# tiny45-button-2-leds.net
KiCad netlist of a schematic drawn in EAGLE
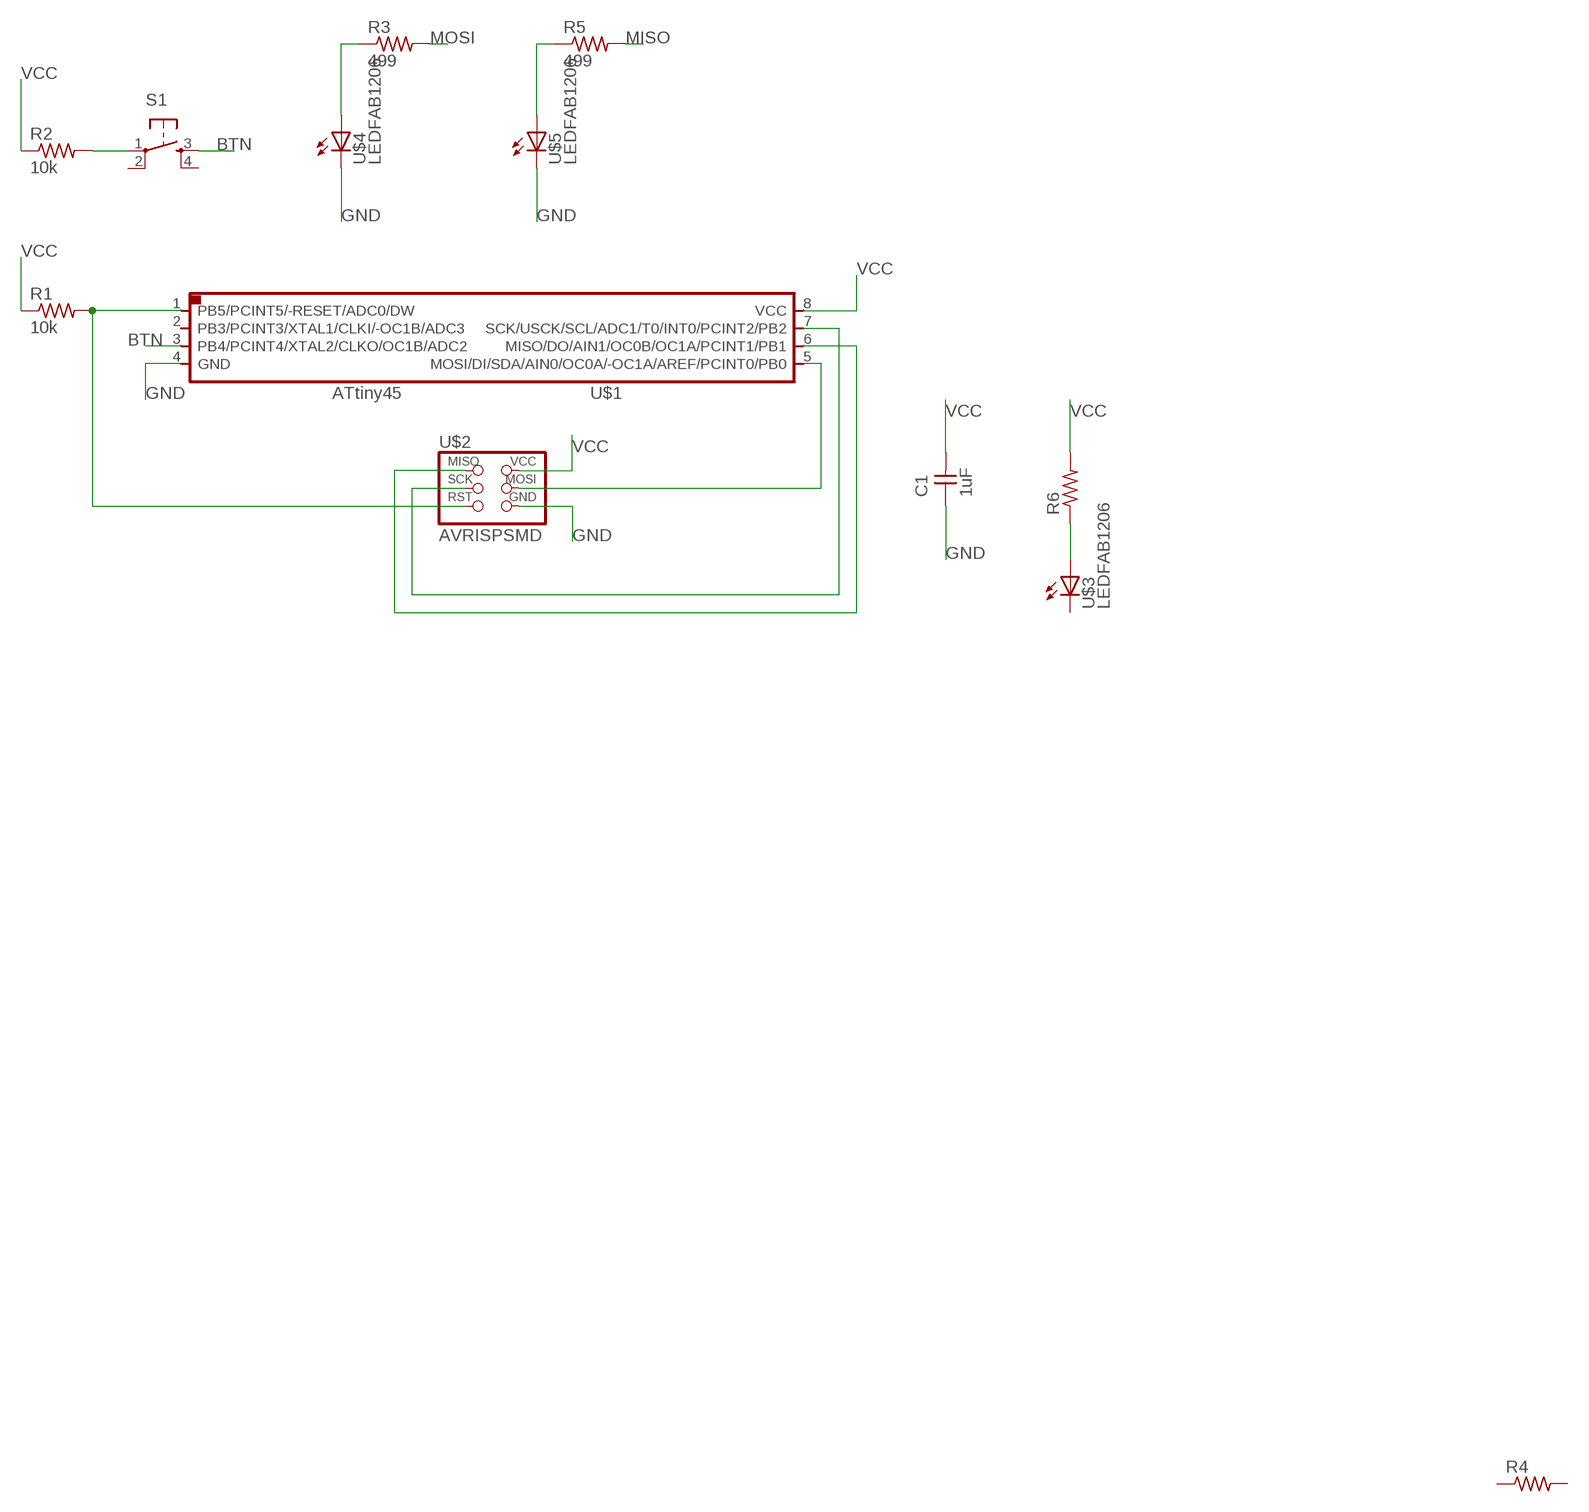
[diagram p0: schematic, sheet 1]

(export (version "E")
  (design (tool "Eeschema 10.0.6"))
  (components
    (comp (ref "C1")
      (value "1uF")
      (footprint "eagle-import:C1206FAB")
      (libsource (lib "eagle-import") (part "CAP-UNPOLARIZEDFAB"))
    )
    (comp (ref "R1")
      (value "10k")
      (footprint "eagle-import:R1206FAB")
      (libsource (lib "eagle-import") (part "RES-US1206FAB"))
    )
    (comp (ref "R2")
      (value "10k")
      (footprint "eagle-import:R1206FAB")
      (libsource (lib "eagle-import") (part "RES-US1206FAB"))
    )
    (comp (ref "R3")
      (value "499")
      (footprint "eagle-import:R1206FAB")
      (libsource (lib "eagle-import") (part "RES-US1206FAB"))
    )
    (comp (ref "R4")
      (value "RES-US1206FAB")
      (footprint "eagle-import:R1206FAB")
      (libsource (lib "eagle-import") (part "RES-US1206FAB"))
    )
    (comp (ref "R5")
      (value "499")
      (footprint "eagle-import:R1206FAB")
      (libsource (lib "eagle-import") (part "RES-US1206FAB"))
    )
    (comp (ref "R6")
      (value "RES-US1206FAB")
      (footprint "eagle-import:R1206FAB")
      (libsource (lib "eagle-import") (part "RES-US1206FAB"))
    )
    (comp (ref "S1")
      (value "6MM_SWITCH6MM_SWITCH")
      (footprint "eagle-import:6MM_SWITCH")
      (libsource (lib "eagle-import") (part "6MM_SWITCH6MM_SWITCH"))
    )
    (comp (ref "U$1")
      (value "ATTINY45SI")
      (footprint "eagle-import:SOIC8")
      (libsource (lib "eagle-import") (part "ATTINY45SI"))
    )
    (comp (ref "U$2")
      (value "AVRISPSMD")
      (footprint "eagle-import:2X03SMD")
      (libsource (lib "eagle-import") (part "AVRISPSMD"))
    )
    (comp (ref "U$3")
      (value "LEDFAB1206")
      (footprint "eagle-import:LED1206FAB")
      (libsource (lib "eagle-import") (part "LEDFAB1206"))
    )
    (comp (ref "U$4")
      (value "LEDFAB1206")
      (footprint "eagle-import:LED1206FAB")
      (libsource (lib "eagle-import") (part "LEDFAB1206"))
    )
    (comp (ref "U$5")
      (value "LEDFAB1206")
      (footprint "eagle-import:LED1206FAB")
      (libsource (lib "eagle-import") (part "LEDFAB1206"))
    )
  )
  (nets
    (net (code "1") (name "/BTN") (class "Default")
      (node (ref "S1") (pin "3") (pinfunction "S_3") (pintype "passive"))
      (node (ref "U$1") (pin "3") (pinfunction "PB4/PCINT4/XTAL2/CLKO/OC1B/ADC2_3") (pintype "bidirectional"))
    )
    (net (code "2") (name "/GND") (class "Default")
      (node (ref "C1") (pin "1") (pinfunction "1_1") (pintype "passive"))
      (node (ref "R6") (pin "1") (pinfunction "1_1") (pintype "passive"))
      (node (ref "U$1") (pin "4") (pinfunction "GND_4") (pintype "bidirectional"))
      (node (ref "U$2") (pin "6") (pinfunction "GND_6") (pintype "passive"))
      (node (ref "U$3") (pin "1") (pinfunction "A_1") (pintype "passive"))
      (node (ref "U$4") (pin "2") (pinfunction "C_2") (pintype "passive"))
      (node (ref "U$5") (pin "2") (pinfunction "C_2") (pintype "passive"))
    )
    (net (code "3") (name "/MISO") (class "Default")
      (node (ref "R5") (pin "2") (pinfunction "2_2") (pintype "passive"))
    )
    (net (code "4") (name "/MOSI") (class "Default")
      (node (ref "R3") (pin "2") (pinfunction "2_2") (pintype "passive"))
    )
    (net (code "5") (name "/VCC") (class "Default")
      (node (ref "C1") (pin "2") (pinfunction "2_2") (pintype "passive"))
      (node (ref "R1") (pin "1") (pinfunction "1_1") (pintype "passive"))
      (node (ref "R2") (pin "1") (pinfunction "1_1") (pintype "passive"))
      (node (ref "R6") (pin "2") (pinfunction "2_2") (pintype "passive"))
      (node (ref "U$1") (pin "8") (pinfunction "VCC_8") (pintype "bidirectional"))
      (node (ref "U$2") (pin "2") (pinfunction "VCC_2") (pintype "passive"))
    )
    (net (code "6") (name "Net-(S1-P)") (class "Default")
      (node (ref "R2") (pin "2") (pinfunction "2_2") (pintype "passive"))
      (node (ref "S1") (pin "1") (pinfunction "P_1") (pintype "passive"))
    )
    (net (code "7") (name "Net-(U$1-MISO{slash}DO{slash}AIN1{slash}OC0B{slash}OC1A{slash}PCINT1{slash}PB1)") (class "Default")
      (node (ref "U$1") (pin "6") (pinfunction "MISO/DO/AIN1/OC0B/OC1A/PCINT1/PB1_6") (pintype "bidirectional"))
      (node (ref "U$2") (pin "1") (pinfunction "MISO_1") (pintype "passive"))
    )
    (net (code "8") (name "Net-(U$1-MOSI{slash}DI{slash}SDA{slash}AIN0{slash}OC0A{slash}-OC1A{slash}AREF{slash}PCINT0{slash}PB0)") (class "Default")
      (node (ref "U$1") (pin "5") (pinfunction "MOSI/DI/SDA/AIN0/OC0A/-OC1A/AREF/PCINT0/PB0_5") (pintype "bidirectional"))
      (node (ref "U$2") (pin "4") (pinfunction "MOSI_4") (pintype "passive"))
    )
    (net (code "9") (name "Net-(U$1-PB5{slash}PCINT5{slash}-RESET{slash}ADC0{slash}DW)") (class "Default")
      (node (ref "R1") (pin "2") (pinfunction "2_2") (pintype "passive"))
      (node (ref "U$1") (pin "1") (pinfunction "PB5/PCINT5/-RESET/ADC0/DW_1") (pintype "bidirectional"))
      (node (ref "U$2") (pin "5") (pinfunction "RST_5") (pintype "passive"))
    )
    (net (code "10") (name "Net-(U$1-SCK{slash}USCK{slash}SCL{slash}ADC1{slash}T0{slash}INT0{slash}PCINT2{slash}PB2)") (class "Default")
      (node (ref "U$1") (pin "7") (pinfunction "SCK/USCK/SCL/ADC1/T0/INT0/PCINT2/PB2_7") (pintype "bidirectional"))
      (node (ref "U$2") (pin "3") (pinfunction "SCK_3") (pintype "passive"))
    )
    (net (code "11") (name "Net-(U$4-A)") (class "Default")
      (node (ref "R3") (pin "1") (pinfunction "1_1") (pintype "passive"))
      (node (ref "U$4") (pin "1") (pinfunction "A_1") (pintype "passive"))
    )
    (net (code "12") (name "Net-(U$5-A)") (class "Default")
      (node (ref "R5") (pin "1") (pinfunction "1_1") (pintype "passive"))
      (node (ref "U$5") (pin "1") (pinfunction "A_1") (pintype "passive"))
    )
    (net (code "13") (name "unconnected-(R4-Pad1)") (class "Default")
      (node (ref "R4") (pin "1") (pinfunction "1_1") (pintype "passive"))
    )
    (net (code "14") (name "unconnected-(R4-Pad2)") (class "Default")
      (node (ref "R4") (pin "2") (pinfunction "2_2") (pintype "passive"))
    )
    (net (code "15") (name "unconnected-(S1-P1-Pad2)") (class "Default")
      (node (ref "S1") (pin "2") (pinfunction "P1_2") (pintype "passive"))
    )
    (net (code "16") (name "unconnected-(S1-S1-Pad4)") (class "Default")
      (node (ref "S1") (pin "4") (pinfunction "S1_4") (pintype "passive"))
    )
    (net (code "17") (name "unconnected-(U$1-PB3{slash}PCINT3{slash}XTAL1{slash}CLKI{slash}-OC1B{slash}ADC3-Pad2)") (class "Default")
      (node (ref "U$1") (pin "2") (pinfunction "PB3/PCINT3/XTAL1/CLKI/-OC1B/ADC3_2") (pintype "bidirectional"))
    )
    (net (code "18") (name "unconnected-(U$3-C-Pad2)") (class "Default")
      (node (ref "U$3") (pin "2") (pinfunction "C_2") (pintype "passive"))
    )
  )
)
